# v1.net
KiCad netlist of a schematic drawn in EAGLE
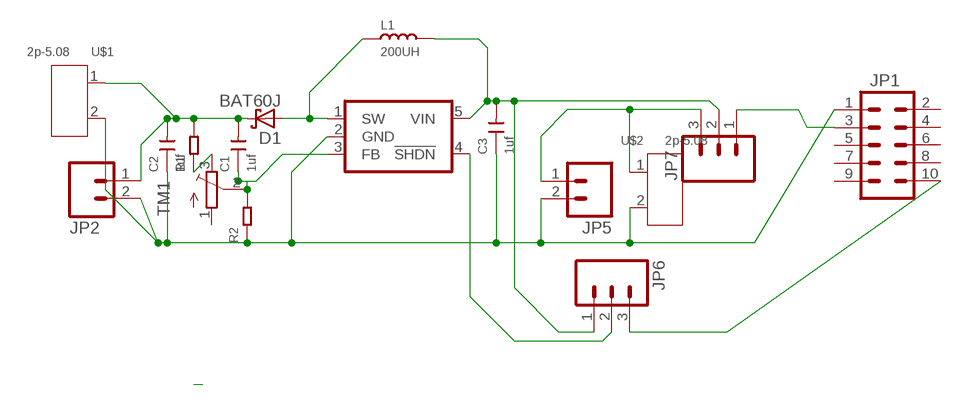
[diagram p0: schematic, sheet 1]

(export (version "E")
  (design (tool "Eeschema 10.0.6"))
  (components
    (comp (ref "C1")
      (value "1uf")
      (footprint "eagle-import:C0805")
      (fields (field (name "MPN") "CC0805KKX7R8BB105"))
      (libsource (lib "eagle-import") (part "CERAMIC-1UF-25V-10%-X7R(0805)"))
    )
    (comp (ref "C2")
      (value "1uf")
      (footprint "eagle-import:C0805")
      (fields (field (name "MPN") "CC0805KKX7R8BB105"))
      (libsource (lib "eagle-import") (part "CERAMIC-1UF-25V-10%-X7R(0805)"))
    )
    (comp (ref "C3")
      (value "1uf")
      (footprint "eagle-import:C0805")
      (fields (field (name "MPN") "CC0805KKX7R8BB105"))
      (libsource (lib "eagle-import") (part "CERAMIC-1UF-25V-10%-X7R(0805)"))
    )
    (comp (ref "D1")
      (value "BAT60J")
      (footprint "eagle-import:SOD323_ST")
      (libsource (lib "eagle-import") (part "BAT60J"))
    )
    (comp (ref "IC1")
      (value "IC_FAN5331-SOT-23-5")
      (footprint "eagle-import:SOT-23-5")
      (libsource (lib "eagle-import") (part "IC_FAN5331-SOT-23-5"))
    )
    (comp (ref "JP1")
      (value "M05X2PTH")
      (footprint "eagle-import:AVR_ICSP")
      (libsource (lib "eagle-import") (part "M05X2PTH"))
    )
    (comp (ref "JP2")
      (value "M02PTH")
      (footprint "eagle-import:1X02")
      (libsource (lib "eagle-import") (part "M02PTH"))
    )
    (comp (ref "JP5")
      (value "M02PTH")
      (footprint "eagle-import:1X02")
      (libsource (lib "eagle-import") (part "M02PTH"))
    )
    (comp (ref "JP6")
      (value "M03PTH")
      (footprint "eagle-import:1X03")
      (libsource (lib "eagle-import") (part "M03PTH"))
    )
    (comp (ref "JP7")
      (value "M03PTH")
      (footprint "eagle-import:1X03")
      (libsource (lib "eagle-import") (part "M03PTH"))
    )
    (comp (ref "L1")
      (value "200UH")
      (footprint "eagle-import:SMD-2P-5.0X5.0X2.0MM")
      (fields (field (name "MPN") "SWPA5020S220MT"))
      (libsource (lib "eagle-import") (part "SMD-INDUCTOR-200UH-20%(2P-5X5MM)"))
    )
    (comp (ref "R1")
      (value "RES-0805")
      (footprint "eagle-import:R0805")
      (libsource (lib "eagle-import") (part "RES-0805"))
    )
    (comp (ref "R2")
      (value "RES-0805")
      (footprint "eagle-import:R0805")
      (libsource (lib "eagle-import") (part "RES-0805"))
    )
    (comp (ref "TM1")
      (value "TRIMPOTTC33X")
      (footprint "eagle-import:TC33X")
      (libsource (lib "eagle-import") (part "TRIMPOTTC33X"))
    )
    (comp (ref "U$1")
      (value "2p-5.08")
      (footprint "eagle-import:H2-5.0-10.5X8.0MM")
      (fields (field (name "MPN") "GS009S-2P-2"))
      (libsource (lib "eagle-import") (part "DIP-BLUE-SCREW-TERMINAL(2P-5.08)"))
    )
    (comp (ref "U$2")
      (value "2p-5.08")
      (footprint "eagle-import:H2-5.0-10.5X8.0MM")
      (fields (field (name "MPN") "GS009S-2P-2"))
      (libsource (lib "eagle-import") (part "DIP-BLUE-SCREW-TERMINAL(2P-5.08)"))
    )
  )
  (nets
    (net (code "1") (name "Net-(C1-Pad2)") (class "Default")
      (node (ref "C1") (pin "2") (pinfunction "2_2") (pintype "passive"))
      (node (ref "C2") (pin "2") (pinfunction "2_2") (pintype "passive"))
      (node (ref "D1") (pin "C") (pinfunction "C_C") (pintype "passive"))
      (node (ref "JP2") (pin "1") (pinfunction "1_1") (pintype "passive"))
      (node (ref "R1") (pin "2") (pinfunction "2_2") (pintype "passive"))
      (node (ref "U$1") (pin "1") (pinfunction "1_1") (pintype "bidirectional"))
    )
    (net (code "2") (name "Net-(IC1-FB)") (class "Default")
      (node (ref "C1") (pin "1") (pinfunction "1_1") (pintype "passive"))
      (node (ref "IC1") (pin "3") (pinfunction "FB_3") (pintype "bidirectional"))
      (node (ref "R2") (pin "2") (pinfunction "2_2") (pintype "passive"))
      (node (ref "TM1") (pin "2") (pinfunction "S_2") (pintype "passive"))
    )
    (net (code "3") (name "Net-(IC1-GND)") (class "Default")
      (node (ref "C2") (pin "1") (pinfunction "1_1") (pintype "passive"))
      (node (ref "C3") (pin "1") (pinfunction "1_1") (pintype "passive"))
      (node (ref "IC1") (pin "2") (pinfunction "GND_2") (pintype "bidirectional"))
      (node (ref "JP1") (pin "1") (pinfunction "1_1") (pintype "passive"))
      (node (ref "JP2") (pin "2") (pinfunction "2_2") (pintype "passive"))
      (node (ref "JP5") (pin "2") (pinfunction "2_2") (pintype "passive"))
      (node (ref "R2") (pin "1") (pinfunction "1_1") (pintype "passive"))
      (node (ref "U$1") (pin "2") (pinfunction "2_2") (pintype "bidirectional"))
      (node (ref "U$2") (pin "2") (pinfunction "2_2") (pintype "bidirectional"))
    )
    (net (code "4") (name "Net-(IC1-SW)") (class "Default")
      (node (ref "D1") (pin "A") (pinfunction "A_A") (pintype "passive"))
      (node (ref "IC1") (pin "1") (pinfunction "SW_1") (pintype "bidirectional"))
      (node (ref "L1") (pin "1") (pinfunction "1_1") (pintype "passive"))
    )
    (net (code "5") (name "Net-(IC1-VIN)") (class "Default")
      (node (ref "C3") (pin "2") (pinfunction "2_2") (pintype "passive"))
      (node (ref "IC1") (pin "5") (pinfunction "VIN_5") (pintype "bidirectional"))
      (node (ref "JP6") (pin "1") (pinfunction "1_1") (pintype "passive"))
      (node (ref "JP7") (pin "2") (pinfunction "2_2") (pintype "passive"))
      (node (ref "L1") (pin "2") (pinfunction "2_2") (pintype "passive"))
    )
    (net (code "6") (name "Net-(IC1-~{SHDN})") (class "Default")
      (node (ref "IC1") (pin "4") (pinfunction "~{SHDN}_4") (pintype "bidirectional"))
      (node (ref "JP6") (pin "2") (pinfunction "2_2") (pintype "passive"))
    )
    (net (code "7") (name "Net-(JP1-Pad3)") (class "Default")
      (node (ref "JP1") (pin "3") (pinfunction "3_3") (pintype "passive"))
      (node (ref "JP7") (pin "1") (pinfunction "1_1") (pintype "passive"))
    )
    (net (code "8") (name "Net-(JP1-Pad10)") (class "Default")
      (node (ref "JP1") (pin "10") (pinfunction "10_10") (pintype "passive"))
      (node (ref "JP6") (pin "3") (pinfunction "3_3") (pintype "passive"))
    )
    (net (code "9") (name "Net-(JP5-Pad1)") (class "Default")
      (node (ref "JP5") (pin "1") (pinfunction "1_1") (pintype "passive"))
      (node (ref "JP7") (pin "3") (pinfunction "3_3") (pintype "passive"))
      (node (ref "U$2") (pin "1") (pinfunction "1_1") (pintype "bidirectional"))
    )
    (net (code "10") (name "Net-(TM1-E)") (class "Default")
      (node (ref "R1") (pin "1") (pinfunction "1_1") (pintype "passive"))
      (node (ref "TM1") (pin "3") (pinfunction "E_3") (pintype "passive"))
    )
    (net (code "11") (name "unconnected-(JP1-Pad2)") (class "Default")
      (node (ref "JP1") (pin "2") (pinfunction "2_2") (pintype "passive"))
    )
    (net (code "12") (name "unconnected-(JP1-Pad4)") (class "Default")
      (node (ref "JP1") (pin "4") (pinfunction "4_4") (pintype "passive"))
    )
    (net (code "13") (name "unconnected-(JP1-Pad5)") (class "Default")
      (node (ref "JP1") (pin "5") (pinfunction "5_5") (pintype "passive"))
    )
    (net (code "14") (name "unconnected-(JP1-Pad6)") (class "Default")
      (node (ref "JP1") (pin "6") (pinfunction "6_6") (pintype "passive"))
    )
    (net (code "15") (name "unconnected-(JP1-Pad7)") (class "Default")
      (node (ref "JP1") (pin "7") (pinfunction "7_7") (pintype "passive"))
    )
    (net (code "16") (name "unconnected-(JP1-Pad8)") (class "Default")
      (node (ref "JP1") (pin "8") (pinfunction "8_8") (pintype "passive"))
    )
    (net (code "17") (name "unconnected-(JP1-Pad9)") (class "Default")
      (node (ref "JP1") (pin "9") (pinfunction "9_9") (pintype "passive"))
    )
    (net (code "18") (name "unconnected-(TM1-A-Pad1)") (class "Default")
      (node (ref "TM1") (pin "1") (pinfunction "A_1") (pintype "passive"))
    )
  )
)
